# G793.net
KiCad netlist of a schematic drawn in EAGLE
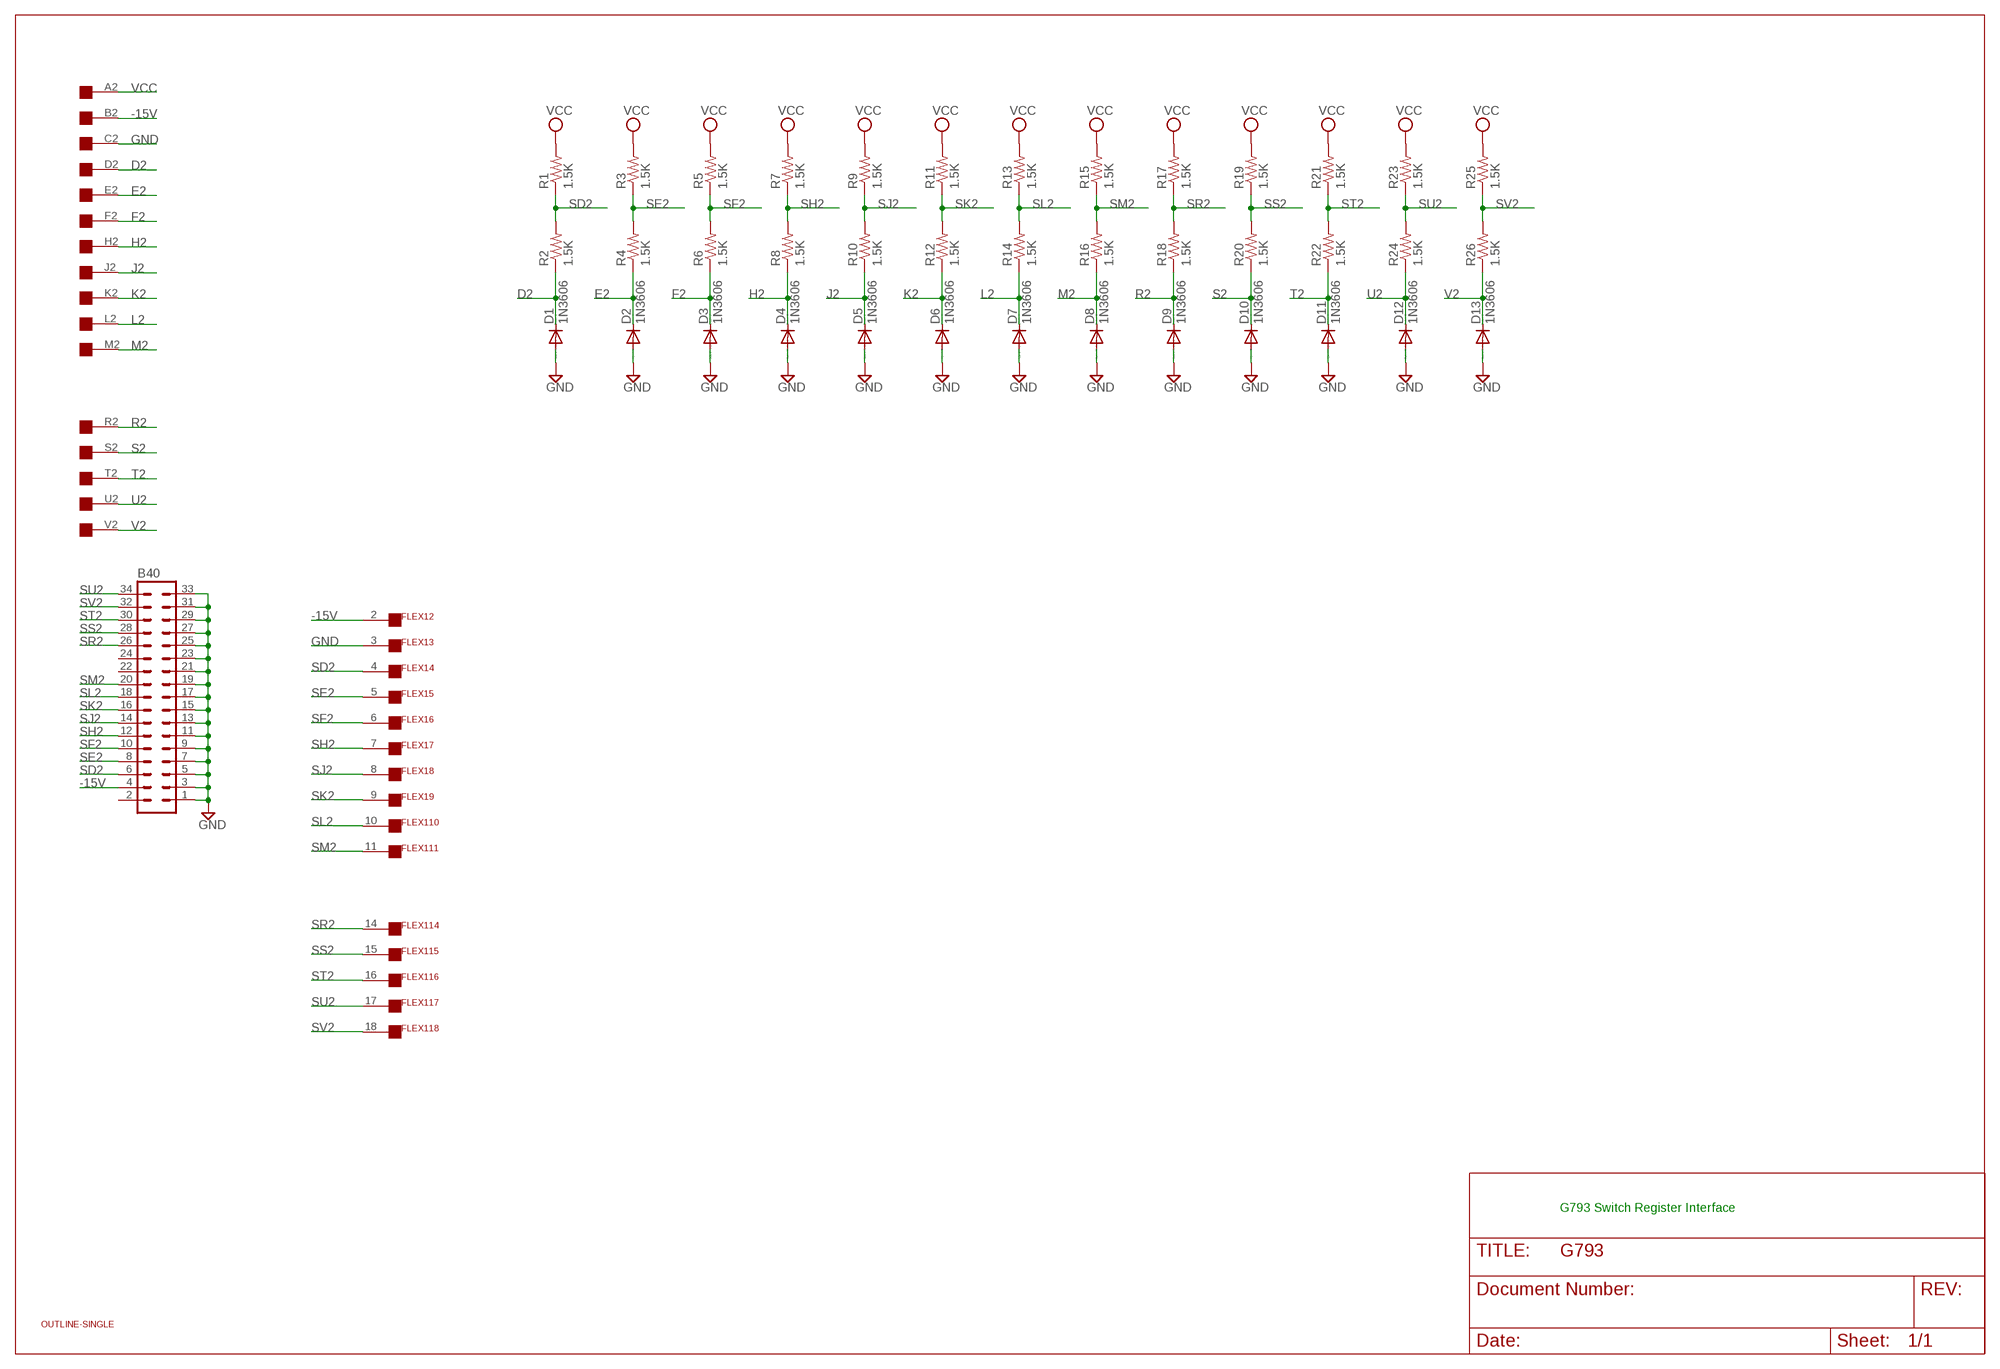
[diagram p0: schematic, sheet 1]

(export (version "E")
  (design (tool "Eeschema 10.0.6"))
  (components
    (comp (ref "B40")
      (value "MA17-2")
      (footprint "eagle-import:MA17-2")
      (libsource (lib "eagle-import") (part "MA17-2"))
    )
    (comp (ref "D1")
      (value "1N3606")
      (footprint "eagle-import:DO35-10")
      (libsource (lib "eagle-import") (part "1N4148DO35-10"))
    )
    (comp (ref "D2")
      (value "1N3606")
      (footprint "eagle-import:DO35-10")
      (libsource (lib "eagle-import") (part "1N4148DO35-10"))
    )
    (comp (ref "D3")
      (value "1N3606")
      (footprint "eagle-import:DO35-10")
      (libsource (lib "eagle-import") (part "1N4148DO35-10"))
    )
    (comp (ref "D4")
      (value "1N3606")
      (footprint "eagle-import:DO35-10")
      (libsource (lib "eagle-import") (part "1N4148DO35-10"))
    )
    (comp (ref "D5")
      (value "1N3606")
      (footprint "eagle-import:DO35-10")
      (libsource (lib "eagle-import") (part "1N4148DO35-10"))
    )
    (comp (ref "D6")
      (value "1N3606")
      (footprint "eagle-import:DO35-10")
      (libsource (lib "eagle-import") (part "1N4148DO35-10"))
    )
    (comp (ref "D7")
      (value "1N3606")
      (footprint "eagle-import:DO35-10")
      (libsource (lib "eagle-import") (part "1N4148DO35-10"))
    )
    (comp (ref "D8")
      (value "1N3606")
      (footprint "eagle-import:DO35-10")
      (libsource (lib "eagle-import") (part "1N4148DO35-10"))
    )
    (comp (ref "D9")
      (value "1N3606")
      (footprint "eagle-import:DO35-10")
      (libsource (lib "eagle-import") (part "1N4148DO35-10"))
    )
    (comp (ref "D10")
      (value "1N3606")
      (footprint "eagle-import:DO35-10")
      (libsource (lib "eagle-import") (part "1N4148DO35-10"))
    )
    (comp (ref "D11")
      (value "1N3606")
      (footprint "eagle-import:DO35-10")
      (libsource (lib "eagle-import") (part "1N4148DO35-10"))
    )
    (comp (ref "D12")
      (value "1N3606")
      (footprint "eagle-import:DO35-10")
      (libsource (lib "eagle-import") (part "1N4148DO35-10"))
    )
    (comp (ref "D13")
      (value "1N3606")
      (footprint "eagle-import:DO35-10")
      (libsource (lib "eagle-import") (part "1N4148DO35-10"))
    )
    (comp (ref "FLEX1")
      (value "FLEX19")
      (footprint "eagle-import:FLEX19")
      (libsource (lib "eagle-import") (part "FLEX19"))
    )
    (comp (ref "R1")
      (value "1.5K")
      (footprint "eagle-import:0207_10")
      (libsource (lib "eagle-import") (part "R-US_0207/10"))
    )
    (comp (ref "R2")
      (value "1.5K")
      (footprint "eagle-import:0207_10")
      (libsource (lib "eagle-import") (part "R-US_0207/10"))
    )
    (comp (ref "R3")
      (value "1.5K")
      (footprint "eagle-import:0207_10")
      (libsource (lib "eagle-import") (part "R-US_0207/10"))
    )
    (comp (ref "R4")
      (value "1.5K")
      (footprint "eagle-import:0207_10")
      (libsource (lib "eagle-import") (part "R-US_0207/10"))
    )
    (comp (ref "R5")
      (value "1.5K")
      (footprint "eagle-import:0207_10")
      (libsource (lib "eagle-import") (part "R-US_0207/10"))
    )
    (comp (ref "R6")
      (value "1.5K")
      (footprint "eagle-import:0207_10")
      (libsource (lib "eagle-import") (part "R-US_0207/10"))
    )
    (comp (ref "R7")
      (value "1.5K")
      (footprint "eagle-import:0207_10")
      (libsource (lib "eagle-import") (part "R-US_0207/10"))
    )
    (comp (ref "R8")
      (value "1.5K")
      (footprint "eagle-import:0207_10")
      (libsource (lib "eagle-import") (part "R-US_0207/10"))
    )
    (comp (ref "R9")
      (value "1.5K")
      (footprint "eagle-import:0207_10")
      (libsource (lib "eagle-import") (part "R-US_0207/10"))
    )
    (comp (ref "R10")
      (value "1.5K")
      (footprint "eagle-import:0207_10")
      (libsource (lib "eagle-import") (part "R-US_0207/10"))
    )
    (comp (ref "R11")
      (value "1.5K")
      (footprint "eagle-import:0207_10")
      (libsource (lib "eagle-import") (part "R-US_0207/10"))
    )
    (comp (ref "R12")
      (value "1.5K")
      (footprint "eagle-import:0207_10")
      (libsource (lib "eagle-import") (part "R-US_0207/10"))
    )
    (comp (ref "R13")
      (value "1.5K")
      (footprint "eagle-import:0207_10")
      (libsource (lib "eagle-import") (part "R-US_0207/10"))
    )
    (comp (ref "R14")
      (value "1.5K")
      (footprint "eagle-import:0207_10")
      (libsource (lib "eagle-import") (part "R-US_0207/10"))
    )
    (comp (ref "R15")
      (value "1.5K")
      (footprint "eagle-import:0207_10")
      (libsource (lib "eagle-import") (part "R-US_0207/10"))
    )
    (comp (ref "R16")
      (value "1.5K")
      (footprint "eagle-import:0207_10")
      (libsource (lib "eagle-import") (part "R-US_0207/10"))
    )
    (comp (ref "R17")
      (value "1.5K")
      (footprint "eagle-import:0207_10")
      (libsource (lib "eagle-import") (part "R-US_0207/10"))
    )
    (comp (ref "R18")
      (value "1.5K")
      (footprint "eagle-import:0207_10")
      (libsource (lib "eagle-import") (part "R-US_0207/10"))
    )
    (comp (ref "R19")
      (value "1.5K")
      (footprint "eagle-import:0207_10")
      (libsource (lib "eagle-import") (part "R-US_0207/10"))
    )
    (comp (ref "R20")
      (value "1.5K")
      (footprint "eagle-import:0207_10")
      (libsource (lib "eagle-import") (part "R-US_0207/10"))
    )
    (comp (ref "R21")
      (value "1.5K")
      (footprint "eagle-import:0207_10")
      (libsource (lib "eagle-import") (part "R-US_0207/10"))
    )
    (comp (ref "R22")
      (value "1.5K")
      (footprint "eagle-import:0207_10")
      (libsource (lib "eagle-import") (part "R-US_0207/10"))
    )
    (comp (ref "R23")
      (value "1.5K")
      (footprint "eagle-import:0207_10")
      (libsource (lib "eagle-import") (part "R-US_0207/10"))
    )
    (comp (ref "R24")
      (value "1.5K")
      (footprint "eagle-import:0207_10")
      (libsource (lib "eagle-import") (part "R-US_0207/10"))
    )
    (comp (ref "R25")
      (value "1.5K")
      (footprint "eagle-import:0207_10")
      (libsource (lib "eagle-import") (part "R-US_0207/10"))
    )
    (comp (ref "R26")
      (value "1.5K")
      (footprint "eagle-import:0207_10")
      (libsource (lib "eagle-import") (part "R-US_0207/10"))
    )
    (comp (ref "U$1")
      (value "OUTLINE-SINGLE")
      (footprint "eagle-import:SINGLE")
      (libsource (lib "eagle-import") (part "OUTLINE-SINGLE"))
    )
    (comp (ref "U$2")
      (value "EDGE-1")
      (footprint "eagle-import:EDGE-CON1")
      (libsource (lib "eagle-import") (part "EDGE-1"))
    )
  )
  (nets
    (net (code "1") (name "/-15V") (class "Default")
      (node (ref "B40") (pin "4") (pinfunction "4_4") (pintype "passive"))
      (node (ref "FLEX1") (pin "2") (pinfunction "1_2") (pintype "passive"))
      (node (ref "U$2") (pin "B2") (pinfunction "1_B2") (pintype "bidirectional"))
    )
    (net (code "2") (name "/D2") (class "Default")
      (node (ref "D1") (pin "C") (pinfunction "C_C") (pintype "passive"))
      (node (ref "R2") (pin "1") (pinfunction "1_1") (pintype "passive"))
      (node (ref "U$2") (pin "D2") (pinfunction "1_D2") (pintype "bidirectional"))
    )
    (net (code "3") (name "/E2") (class "Default")
      (node (ref "D2") (pin "C") (pinfunction "C_C") (pintype "passive"))
      (node (ref "R4") (pin "1") (pinfunction "1_1") (pintype "passive"))
      (node (ref "U$2") (pin "E2") (pinfunction "1_E2") (pintype "bidirectional"))
    )
    (net (code "4") (name "/F2") (class "Default")
      (node (ref "D3") (pin "C") (pinfunction "C_C") (pintype "passive"))
      (node (ref "R6") (pin "1") (pinfunction "1_1") (pintype "passive"))
      (node (ref "U$2") (pin "F2") (pinfunction "1_F2") (pintype "bidirectional"))
    )
    (net (code "5") (name "/H2") (class "Default")
      (node (ref "D4") (pin "C") (pinfunction "C_C") (pintype "passive"))
      (node (ref "R8") (pin "1") (pinfunction "1_1") (pintype "passive"))
      (node (ref "U$2") (pin "H2") (pinfunction "1_H2") (pintype "bidirectional"))
    )
    (net (code "6") (name "/J2") (class "Default")
      (node (ref "D5") (pin "C") (pinfunction "C_C") (pintype "passive"))
      (node (ref "R10") (pin "1") (pinfunction "1_1") (pintype "passive"))
      (node (ref "U$2") (pin "J2") (pinfunction "1_J2") (pintype "bidirectional"))
    )
    (net (code "7") (name "/K2") (class "Default")
      (node (ref "D6") (pin "C") (pinfunction "C_C") (pintype "passive"))
      (node (ref "R12") (pin "1") (pinfunction "1_1") (pintype "passive"))
      (node (ref "U$2") (pin "K2") (pinfunction "1_K2") (pintype "bidirectional"))
    )
    (net (code "8") (name "/L2") (class "Default")
      (node (ref "D7") (pin "C") (pinfunction "C_C") (pintype "passive"))
      (node (ref "R14") (pin "1") (pinfunction "1_1") (pintype "passive"))
      (node (ref "U$2") (pin "L2") (pinfunction "1_L2") (pintype "bidirectional"))
    )
    (net (code "9") (name "/M2") (class "Default")
      (node (ref "D8") (pin "C") (pinfunction "C_C") (pintype "passive"))
      (node (ref "R16") (pin "1") (pinfunction "1_1") (pintype "passive"))
      (node (ref "U$2") (pin "M2") (pinfunction "1_M2") (pintype "bidirectional"))
    )
    (net (code "10") (name "/R2") (class "Default")
      (node (ref "D9") (pin "C") (pinfunction "C_C") (pintype "passive"))
      (node (ref "R18") (pin "1") (pinfunction "1_1") (pintype "passive"))
      (node (ref "U$2") (pin "R2") (pinfunction "1_R2") (pintype "bidirectional"))
    )
    (net (code "11") (name "/S2") (class "Default")
      (node (ref "D10") (pin "C") (pinfunction "C_C") (pintype "passive"))
      (node (ref "R20") (pin "1") (pinfunction "1_1") (pintype "passive"))
      (node (ref "U$2") (pin "S2") (pinfunction "1_S2") (pintype "bidirectional"))
    )
    (net (code "12") (name "/SD2") (class "Default")
      (node (ref "B40") (pin "6") (pinfunction "6_6") (pintype "passive"))
      (node (ref "FLEX1") (pin "4") (pinfunction "1_4") (pintype "passive"))
      (node (ref "R1") (pin "1") (pinfunction "1_1") (pintype "passive"))
      (node (ref "R2") (pin "2") (pinfunction "2_2") (pintype "passive"))
    )
    (net (code "13") (name "/SE2") (class "Default")
      (node (ref "B40") (pin "8") (pinfunction "8_8") (pintype "passive"))
      (node (ref "FLEX1") (pin "5") (pinfunction "1_5") (pintype "passive"))
      (node (ref "R3") (pin "1") (pinfunction "1_1") (pintype "passive"))
      (node (ref "R4") (pin "2") (pinfunction "2_2") (pintype "passive"))
    )
    (net (code "14") (name "/SF2") (class "Default")
      (node (ref "B40") (pin "10") (pinfunction "10_10") (pintype "passive"))
      (node (ref "FLEX1") (pin "6") (pinfunction "1_6") (pintype "passive"))
      (node (ref "R5") (pin "1") (pinfunction "1_1") (pintype "passive"))
      (node (ref "R6") (pin "2") (pinfunction "2_2") (pintype "passive"))
    )
    (net (code "15") (name "/SH2") (class "Default")
      (node (ref "B40") (pin "12") (pinfunction "12_12") (pintype "passive"))
      (node (ref "FLEX1") (pin "7") (pinfunction "1_7") (pintype "passive"))
      (node (ref "R7") (pin "1") (pinfunction "1_1") (pintype "passive"))
      (node (ref "R8") (pin "2") (pinfunction "2_2") (pintype "passive"))
    )
    (net (code "16") (name "/SJ2") (class "Default")
      (node (ref "B40") (pin "14") (pinfunction "14_14") (pintype "passive"))
      (node (ref "FLEX1") (pin "8") (pinfunction "1_8") (pintype "passive"))
      (node (ref "R10") (pin "2") (pinfunction "2_2") (pintype "passive"))
      (node (ref "R9") (pin "1") (pinfunction "1_1") (pintype "passive"))
    )
    (net (code "17") (name "/SK2") (class "Default")
      (node (ref "B40") (pin "16") (pinfunction "16_16") (pintype "passive"))
      (node (ref "FLEX1") (pin "9") (pinfunction "1_9") (pintype "passive"))
      (node (ref "R11") (pin "1") (pinfunction "1_1") (pintype "passive"))
      (node (ref "R12") (pin "2") (pinfunction "2_2") (pintype "passive"))
    )
    (net (code "18") (name "/SL2") (class "Default")
      (node (ref "B40") (pin "18") (pinfunction "18_18") (pintype "passive"))
      (node (ref "FLEX1") (pin "10") (pinfunction "1_10") (pintype "passive"))
      (node (ref "R13") (pin "1") (pinfunction "1_1") (pintype "passive"))
      (node (ref "R14") (pin "2") (pinfunction "2_2") (pintype "passive"))
    )
    (net (code "19") (name "/SM2") (class "Default")
      (node (ref "B40") (pin "20") (pinfunction "20_20") (pintype "passive"))
      (node (ref "FLEX1") (pin "11") (pinfunction "1_11") (pintype "passive"))
      (node (ref "R15") (pin "1") (pinfunction "1_1") (pintype "passive"))
      (node (ref "R16") (pin "2") (pinfunction "2_2") (pintype "passive"))
    )
    (net (code "20") (name "/SR2") (class "Default")
      (node (ref "B40") (pin "26") (pinfunction "26_26") (pintype "passive"))
      (node (ref "FLEX1") (pin "14") (pinfunction "1_14") (pintype "passive"))
      (node (ref "R17") (pin "1") (pinfunction "1_1") (pintype "passive"))
      (node (ref "R18") (pin "2") (pinfunction "2_2") (pintype "passive"))
    )
    (net (code "21") (name "/SS2") (class "Default")
      (node (ref "B40") (pin "28") (pinfunction "28_28") (pintype "passive"))
      (node (ref "FLEX1") (pin "15") (pinfunction "1_15") (pintype "passive"))
      (node (ref "R19") (pin "1") (pinfunction "1_1") (pintype "passive"))
      (node (ref "R20") (pin "2") (pinfunction "2_2") (pintype "passive"))
    )
    (net (code "22") (name "/ST2") (class "Default")
      (node (ref "B40") (pin "30") (pinfunction "30_30") (pintype "passive"))
      (node (ref "FLEX1") (pin "16") (pinfunction "1_16") (pintype "passive"))
      (node (ref "R21") (pin "1") (pinfunction "1_1") (pintype "passive"))
      (node (ref "R22") (pin "2") (pinfunction "2_2") (pintype "passive"))
    )
    (net (code "23") (name "/SU2") (class "Default")
      (node (ref "B40") (pin "34") (pinfunction "34_34") (pintype "passive"))
      (node (ref "FLEX1") (pin "17") (pinfunction "1_17") (pintype "passive"))
      (node (ref "R23") (pin "1") (pinfunction "1_1") (pintype "passive"))
      (node (ref "R24") (pin "2") (pinfunction "2_2") (pintype "passive"))
    )
    (net (code "24") (name "/SV2") (class "Default")
      (node (ref "B40") (pin "32") (pinfunction "32_32") (pintype "passive"))
      (node (ref "FLEX1") (pin "18") (pinfunction "1_18") (pintype "passive"))
      (node (ref "R25") (pin "1") (pinfunction "1_1") (pintype "passive"))
      (node (ref "R26") (pin "2") (pinfunction "2_2") (pintype "passive"))
    )
    (net (code "25") (name "/T2") (class "Default")
      (node (ref "D11") (pin "C") (pinfunction "C_C") (pintype "passive"))
      (node (ref "R22") (pin "1") (pinfunction "1_1") (pintype "passive"))
      (node (ref "U$2") (pin "T2") (pinfunction "1_T2") (pintype "bidirectional"))
    )
    (net (code "26") (name "/U2") (class "Default")
      (node (ref "D12") (pin "C") (pinfunction "C_C") (pintype "passive"))
      (node (ref "R24") (pin "1") (pinfunction "1_1") (pintype "passive"))
      (node (ref "U$2") (pin "U2") (pinfunction "1_U2") (pintype "bidirectional"))
    )
    (net (code "27") (name "/V2") (class "Default")
      (node (ref "D13") (pin "C") (pinfunction "C_C") (pintype "passive"))
      (node (ref "R26") (pin "1") (pinfunction "1_1") (pintype "passive"))
      (node (ref "U$2") (pin "V2") (pinfunction "1_V2") (pintype "bidirectional"))
    )
    (net (code "28") (name "GND") (class "Default")
      (node (ref "B40") (pin "1") (pinfunction "1_1") (pintype "passive"))
      (node (ref "B40") (pin "11") (pinfunction "11_11") (pintype "passive"))
      (node (ref "B40") (pin "13") (pinfunction "13_13") (pintype "passive"))
      (node (ref "B40") (pin "15") (pinfunction "15_15") (pintype "passive"))
      (node (ref "B40") (pin "17") (pinfunction "17_17") (pintype "passive"))
      (node (ref "B40") (pin "19") (pinfunction "19_19") (pintype "passive"))
      (node (ref "B40") (pin "21") (pinfunction "21_21") (pintype "passive"))
      (node (ref "B40") (pin "23") (pinfunction "23_23") (pintype "passive"))
      (node (ref "B40") (pin "25") (pinfunction "25_25") (pintype "passive"))
      (node (ref "B40") (pin "27") (pinfunction "27_27") (pintype "passive"))
      (node (ref "B40") (pin "29") (pinfunction "29_29") (pintype "passive"))
      (node (ref "B40") (pin "3") (pinfunction "3_3") (pintype "passive"))
      (node (ref "B40") (pin "31") (pinfunction "31_31") (pintype "passive"))
      (node (ref "B40") (pin "33") (pinfunction "33_33") (pintype "passive"))
      (node (ref "B40") (pin "5") (pinfunction "5_5") (pintype "passive"))
      (node (ref "B40") (pin "7") (pinfunction "7_7") (pintype "passive"))
      (node (ref "B40") (pin "9") (pinfunction "9_9") (pintype "passive"))
      (node (ref "D1") (pin "A") (pinfunction "A_A") (pintype "passive"))
      (node (ref "D10") (pin "A") (pinfunction "A_A") (pintype "passive"))
      (node (ref "D11") (pin "A") (pinfunction "A_A") (pintype "passive"))
      (node (ref "D12") (pin "A") (pinfunction "A_A") (pintype "passive"))
      (node (ref "D13") (pin "A") (pinfunction "A_A") (pintype "passive"))
      (node (ref "D2") (pin "A") (pinfunction "A_A") (pintype "passive"))
      (node (ref "D3") (pin "A") (pinfunction "A_A") (pintype "passive"))
      (node (ref "D4") (pin "A") (pinfunction "A_A") (pintype "passive"))
      (node (ref "D5") (pin "A") (pinfunction "A_A") (pintype "passive"))
      (node (ref "D6") (pin "A") (pinfunction "A_A") (pintype "passive"))
      (node (ref "D7") (pin "A") (pinfunction "A_A") (pintype "passive"))
      (node (ref "D8") (pin "A") (pinfunction "A_A") (pintype "passive"))
      (node (ref "D9") (pin "A") (pinfunction "A_A") (pintype "passive"))
      (node (ref "FLEX1") (pin "3") (pinfunction "1_3") (pintype "passive"))
      (node (ref "U$2") (pin "C2") (pinfunction "1_C2") (pintype "bidirectional"))
    )
    (net (code "29") (name "VCC") (class "Default")
      (node (ref "R1") (pin "2") (pinfunction "2_2") (pintype "passive"))
      (node (ref "R11") (pin "2") (pinfunction "2_2") (pintype "passive"))
      (node (ref "R13") (pin "2") (pinfunction "2_2") (pintype "passive"))
      (node (ref "R15") (pin "2") (pinfunction "2_2") (pintype "passive"))
      (node (ref "R17") (pin "2") (pinfunction "2_2") (pintype "passive"))
      (node (ref "R19") (pin "2") (pinfunction "2_2") (pintype "passive"))
      (node (ref "R21") (pin "2") (pinfunction "2_2") (pintype "passive"))
      (node (ref "R23") (pin "2") (pinfunction "2_2") (pintype "passive"))
      (node (ref "R25") (pin "2") (pinfunction "2_2") (pintype "passive"))
      (node (ref "R3") (pin "2") (pinfunction "2_2") (pintype "passive"))
      (node (ref "R5") (pin "2") (pinfunction "2_2") (pintype "passive"))
      (node (ref "R7") (pin "2") (pinfunction "2_2") (pintype "passive"))
      (node (ref "R9") (pin "2") (pinfunction "2_2") (pintype "passive"))
      (node (ref "U$2") (pin "A2") (pinfunction "1_A2") (pintype "bidirectional"))
    )
    (net (code "30") (name "unconnected-(B40-Pad2)") (class "Default")
      (node (ref "B40") (pin "2") (pinfunction "2_2") (pintype "passive"))
    )
    (net (code "31") (name "unconnected-(B40-Pad22)") (class "Default")
      (node (ref "B40") (pin "22") (pinfunction "22_22") (pintype "passive"))
    )
    (net (code "32") (name "unconnected-(B40-Pad24)") (class "Default")
      (node (ref "B40") (pin "24") (pinfunction "24_24") (pintype "passive"))
    )
  )
)
